# Sheet1.net
KiCad netlist of a schematic drawn in Altium Designer
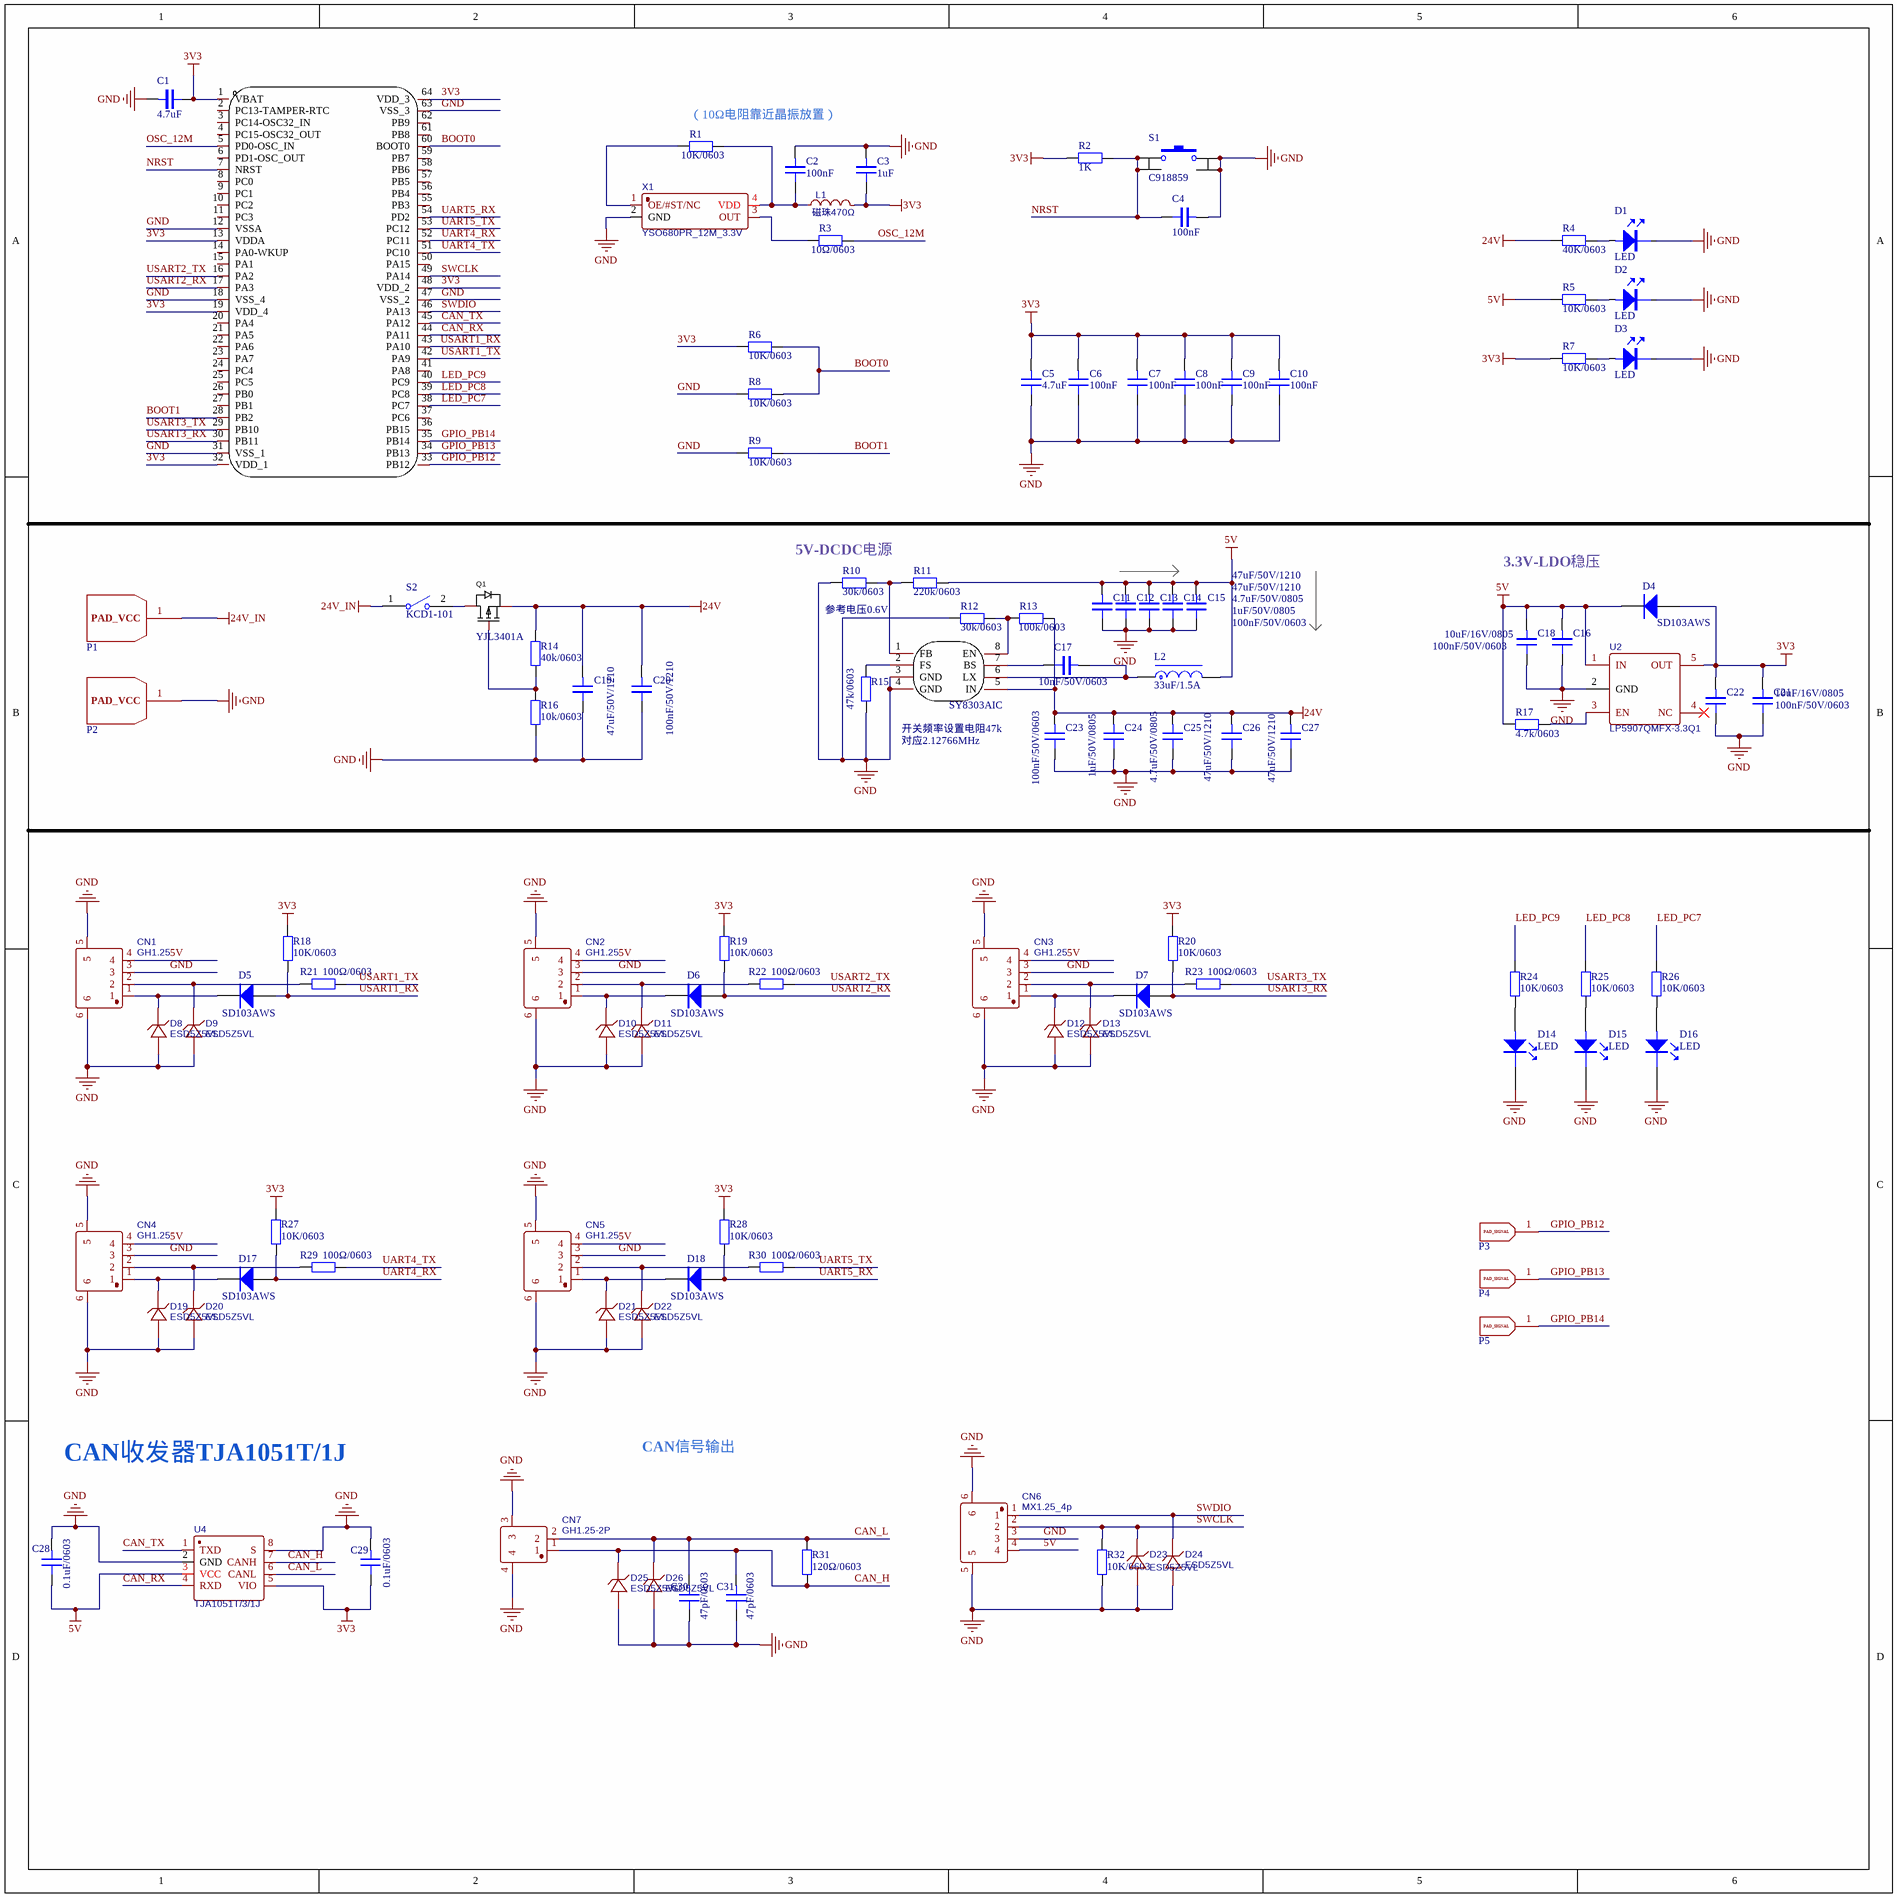
[diagram p0: Sheet1.SchDoc]

(export (version "E")
  (design (tool "Eeschema 10.0.6"))
  (components
    (comp (ref "C1")
      (value "4.7uF")
      (footprint "C 0603_L")
      (description "陶瓷电容")
      (libsource (lib "HERO_通用") (part "CAP"))
    )
    (comp (ref "C2")
      (value "100nF")
      (footprint "C 0603_L")
      (description "陶瓷电容")
      (libsource (lib "HERO_通用") (part "CAP"))
    )
    (comp (ref "C3")
      (value "1uF")
      (footprint "C 0603_L")
      (description "陶瓷电容")
      (libsource (lib "HERO_通用") (part "CAP"))
    )
    (comp (ref "C4")
      (value "100nF")
      (footprint "C 0603_L")
      (description "陶瓷电容")
      (libsource (lib "HERO_通用") (part "CAP"))
    )
    (comp (ref "C5")
      (value "4.7uF")
      (footprint "C 0603_L")
      (description "陶瓷电容")
      (libsource (lib "HERO_通用") (part "CAP"))
    )
    (comp (ref "C6")
      (value "100nF")
      (footprint "C 0603_L")
      (description "陶瓷电容")
      (libsource (lib "HERO_通用") (part "CAP"))
    )
    (comp (ref "C7")
      (value "100nF")
      (footprint "C 0603_L")
      (description "陶瓷电容")
      (libsource (lib "HERO_通用") (part "CAP"))
    )
    (comp (ref "C8")
      (value "100nF")
      (footprint "C 0603_L")
      (description "陶瓷电容")
      (libsource (lib "HERO_通用") (part "CAP"))
    )
    (comp (ref "C9")
      (value "100nF")
      (footprint "C 0603_L")
      (description "陶瓷电容")
      (libsource (lib "HERO_通用") (part "CAP"))
    )
    (comp (ref "C10")
      (value "100nF")
      (footprint "C 0603_L")
      (description "陶瓷电容")
      (libsource (lib "HERO_通用") (part "CAP"))
    )
    (comp (ref "C11")
      (value "47uF/50V/1210")
      (footprint "C 1210_L")
      (description "陶瓷电容")
      (libsource (lib "HERO_通用") (part "CAP"))
    )
    (comp (ref "C12")
      (value "47uF/50V/1210")
      (footprint "C 1210_L")
      (description "陶瓷电容")
      (libsource (lib "HERO_通用") (part "CAP"))
    )
    (comp (ref "C13")
      (value "4.7uF/50V/0805")
      (footprint "C 0805_L")
      (description "陶瓷电容")
      (libsource (lib "HERO_通用") (part "CAP"))
    )
    (comp (ref "C14")
      (value "1uF/50V/0805")
      (footprint "C 0805_L")
      (description "陶瓷电容")
      (libsource (lib "HERO_通用") (part "CAP"))
    )
    (comp (ref "C15")
      (value "100nF/50V/0603")
      (footprint "C 0603_L")
      (description "陶瓷电容")
      (libsource (lib "HERO_通用") (part "CAP"))
    )
    (comp (ref "C16")
      (value "100nF/50V/0603")
      (footprint "C 0603_L")
      (description "Capacitor")
      (libsource (lib "DJI_Armer") (part "CAP"))
    )
    (comp (ref "C17")
      (value "10nF/50V/0603")
      (footprint "C 0603_L")
      (description "陶瓷电容")
      (libsource (lib "HERO_通用") (part "CAP"))
    )
    (comp (ref "C18")
      (value "10uF/16V/0805")
      (footprint "C 0805_L")
      (description "陶瓷电容")
      (libsource (lib "HERO_通用") (part "CAP"))
    )
    (comp (ref "C19")
      (value "47uF/50V/1210")
      (footprint "C 1210_L")
      (description "陶瓷电容")
      (libsource (lib "HERO_通用") (part "CAP"))
    )
    (comp (ref "C20")
      (value "100nF/50V/1210")
      (footprint "C 0603_L")
      (description "陶瓷电容")
      (libsource (lib "HERO_通用") (part "CAP"))
    )
    (comp (ref "C21")
      (value "100nF/50V/0603")
      (footprint "C 0603_L")
      (description "Capacitor")
      (libsource (lib "DJI_Armer") (part "CAP"))
    )
    (comp (ref "C22")
      (value "10uF/16V/0805")
      (footprint "C 0805_L")
      (description "陶瓷电容")
      (libsource (lib "HERO_通用") (part "CAP"))
    )
    (comp (ref "C23")
      (value "100nF/50V/0603")
      (footprint "C 0603_L")
      (description "陶瓷电容")
      (libsource (lib "HERO_通用") (part "CAP"))
    )
    (comp (ref "C24")
      (value "1uF/50V/0805")
      (footprint "C 0805_L")
      (description "陶瓷电容")
      (libsource (lib "HERO_通用") (part "CAP"))
    )
    (comp (ref "C25")
      (value "4.7uF/50V/0805")
      (footprint "C 0805_L")
      (description "陶瓷电容")
      (libsource (lib "HERO_通用") (part "CAP"))
    )
    (comp (ref "C26")
      (value "47uF/50V/1210")
      (footprint "C 1210_L")
      (description "陶瓷电容")
      (libsource (lib "HERO_通用") (part "CAP"))
    )
    (comp (ref "C27")
      (value "47uF/50V/1210")
      (footprint "C 1210_L")
      (description "陶瓷电容")
      (libsource (lib "HERO_通用") (part "CAP"))
    )
    (comp (ref "C28")
      (value "0.1uF/0603")
      (footprint "C 0603_L")
      (description "陶瓷电容")
      (libsource (lib "HERO_通用") (part "CAP"))
    )
    (comp (ref "C29")
      (value "0.1uF/0603")
      (footprint "C 0603_L")
      (description "陶瓷电容")
      (libsource (lib "HERO_通用") (part "CAP"))
    )
    (comp (ref "C30")
      (value "47pF/0603")
      (footprint "C 0603_L")
      (description "陶瓷电容")
      (libsource (lib "HERO_通用") (part "CAP"))
    )
    (comp (ref "C31")
      (value "47pF/0603")
      (footprint "C 0603_L")
      (description "陶瓷电容")
      (libsource (lib "HERO_通用") (part "CAP"))
    )
    (comp (ref "CN1")
      (value "GH1.25")
      (footprint "GH1.25 4P-WT")
      (description "连接端子")
      (fields
        (field (name "BOM_SUPPLIER PART") "C225127")
        (field (name "BOM_MANUFACTURER PART") "A1257WR-S-4P")
        (field (name "CONTRIBUTOR") "LCSC")
      )
      (libsource (lib "HERO_交互") (part "GH1.25 4p"))
    )
    (comp (ref "CN2")
      (value "GH1.25")
      (footprint "GH1.25 4P-WT")
      (description "连接端子")
      (fields
        (field (name "BOM_SUPPLIER PART") "C225127")
        (field (name "BOM_MANUFACTURER PART") "A1257WR-S-4P")
        (field (name "CONTRIBUTOR") "LCSC")
      )
      (libsource (lib "HERO_交互") (part "GH1.25 4p"))
    )
    (comp (ref "CN3")
      (value "GH1.25")
      (footprint "GH1.25 4P-WT")
      (description "连接端子")
      (fields
        (field (name "BOM_SUPPLIER PART") "C225127")
        (field (name "BOM_MANUFACTURER PART") "A1257WR-S-4P")
        (field (name "CONTRIBUTOR") "LCSC")
      )
      (libsource (lib "HERO_交互") (part "GH1.25 4p"))
    )
    (comp (ref "CN4")
      (value "GH1.25")
      (footprint "GH1.25 4P-WT")
      (description "连接端子")
      (fields
        (field (name "BOM_SUPPLIER PART") "C225127")
        (field (name "BOM_MANUFACTURER PART") "A1257WR-S-4P")
        (field (name "CONTRIBUTOR") "LCSC")
      )
      (libsource (lib "HERO_交互") (part "GH1.25 4p"))
    )
    (comp (ref "CN5")
      (value "GH1.25")
      (footprint "GH1.25 4P-WT")
      (description "连接端子")
      (fields
        (field (name "BOM_SUPPLIER PART") "C225127")
        (field (name "BOM_MANUFACTURER PART") "A1257WR-S-4P")
        (field (name "CONTRIBUTOR") "LCSC")
      )
      (libsource (lib "HERO_交互") (part "GH1.25 4p"))
    )
    (comp (ref "CN6")
      (value "MX1.25_4p")
      (footprint "MX1.25_4PIN")
      (description "连接端子")
      (fields
        (field (name "BOM_SUPPLIER PART") "C225127")
        (field (name "BOM_MANUFACTURER PART") "A1257WR-S-4P")
        (field (name "CONTRIBUTOR") "LCSC")
      )
      (libsource (lib "HERO_交互") (part "MX1.25_4p"))
    )
    (comp (ref "CN7")
      (value "GH1.25-2P")
      (footprint "GH1.25-2P-LT")
      (description "连接端子")
      (fields
        (field (name "BOM_SUPPLIER PART") "C225125")
        (field (name "BOM_MANUFACTURER PART") "A1257WR-S-2P")
        (field (name "CONTRIBUTOR") "LCSC")
      )
      (libsource (lib "HERO_交互") (part "GH1.25-2P"))
    )
    (comp (ref "D1")
      (value "LED")
      (footprint "LED_0603")
      (description "发光二极管")
      (libsource (lib "") (part "LED_1"))
    )
    (comp (ref "D2")
      (value "LED")
      (footprint "LED_0603")
      (description "发光二极管")
      (libsource (lib "") (part "LED_1"))
    )
    (comp (ref "D3")
      (value "LED")
      (footprint "LED_0603")
      (description "发光二极管")
      (libsource (lib "") (part "LED_1"))
    )
    (comp (ref "D4")
      (value "SD103AWS")
      (footprint "SOD-323")
      (description "二极管")
      (libsource (lib "DJI_Armer") (part "SD103AWS"))
    )
    (comp (ref "D5")
      (value "SD103AWS")
      (footprint "SOD-323")
      (description "二极管")
      (libsource (lib "DJI_Armer") (part "SD103AWS"))
    )
    (comp (ref "D6")
      (value "SD103AWS")
      (footprint "SOD-323")
      (description "二极管")
      (libsource (lib "DJI_Armer") (part "SD103AWS"))
    )
    (comp (ref "D7")
      (value "SD103AWS")
      (footprint "SOD-323")
      (description "二极管")
      (libsource (lib "DJI_Armer") (part "SD103AWS"))
    )
    (comp (ref "D8")
      (value "ESD5Z5VL")
      (footprint "SOD-523")
      (description "ESD 单向 5V")
      (fields
        (field (name "BOM_MANUFACTURER PART") "SMF6.5A")
        (field (name "BOM_SUPPLIER PART") "C123792")
        (field (name "CONTRIBUTOR") "LCSC")
      )
      (libsource (lib "HERO_通用") (part "ESD5Z5VL"))
    )
    (comp (ref "D9")
      (value "ESD5Z5VL")
      (footprint "SOD-523")
      (description "ESD 单向 5V")
      (fields
        (field (name "BOM_MANUFACTURER PART") "SMF6.5A")
        (field (name "BOM_SUPPLIER PART") "C123792")
        (field (name "CONTRIBUTOR") "LCSC")
      )
      (libsource (lib "HERO_通用") (part "ESD5Z5VL"))
    )
    (comp (ref "D10")
      (value "ESD5Z5VL")
      (footprint "SOD-523")
      (description "ESD 单向 5V")
      (fields
        (field (name "BOM_MANUFACTURER PART") "SMF6.5A")
        (field (name "BOM_SUPPLIER PART") "C123792")
        (field (name "CONTRIBUTOR") "LCSC")
      )
      (libsource (lib "HERO_通用") (part "ESD5Z5VL"))
    )
    (comp (ref "D11")
      (value "ESD5Z5VL")
      (footprint "SOD-523")
      (description "ESD 单向 5V")
      (fields
        (field (name "BOM_MANUFACTURER PART") "SMF6.5A")
        (field (name "BOM_SUPPLIER PART") "C123792")
        (field (name "CONTRIBUTOR") "LCSC")
      )
      (libsource (lib "HERO_通用") (part "ESD5Z5VL"))
    )
    (comp (ref "D12")
      (value "ESD5Z5VL")
      (footprint "SOD-523")
      (description "ESD 单向 5V")
      (fields
        (field (name "BOM_MANUFACTURER PART") "SMF6.5A")
        (field (name "BOM_SUPPLIER PART") "C123792")
        (field (name "CONTRIBUTOR") "LCSC")
      )
      (libsource (lib "HERO_通用") (part "ESD5Z5VL"))
    )
    (comp (ref "D13")
      (value "ESD5Z5VL")
      (footprint "SOD-523")
      (description "ESD 单向 5V")
      (fields
        (field (name "BOM_MANUFACTURER PART") "SMF6.5A")
        (field (name "BOM_SUPPLIER PART") "C123792")
        (field (name "CONTRIBUTOR") "LCSC")
      )
      (libsource (lib "HERO_通用") (part "ESD5Z5VL"))
    )
    (comp (ref "D14")
      (value "LED")
      (footprint "LED_0603")
      (description "发光二极管")
      (libsource (lib "HERO_通用") (part "LED"))
    )
    (comp (ref "D15")
      (value "LED")
      (footprint "LED_0603")
      (description "发光二极管")
      (libsource (lib "HERO_通用") (part "LED"))
    )
    (comp (ref "D16")
      (value "LED")
      (footprint "LED_0603")
      (description "发光二极管")
      (libsource (lib "HERO_通用") (part "LED"))
    )
    (comp (ref "D17")
      (value "SD103AWS")
      (footprint "SOD-323")
      (description "二极管")
      (libsource (lib "DJI_Armer") (part "SD103AWS"))
    )
    (comp (ref "D18")
      (value "SD103AWS")
      (footprint "SOD-323")
      (description "二极管")
      (libsource (lib "DJI_Armer") (part "SD103AWS"))
    )
    (comp (ref "D19")
      (value "ESD5Z5VL")
      (footprint "SOD-523")
      (description "ESD 单向 5V")
      (fields
        (field (name "BOM_MANUFACTURER PART") "SMF6.5A")
        (field (name "BOM_SUPPLIER PART") "C123792")
        (field (name "CONTRIBUTOR") "LCSC")
      )
      (libsource (lib "HERO_通用") (part "ESD5Z5VL"))
    )
    (comp (ref "D20")
      (value "ESD5Z5VL")
      (footprint "SOD-523")
      (description "ESD 单向 5V")
      (fields
        (field (name "BOM_MANUFACTURER PART") "SMF6.5A")
        (field (name "BOM_SUPPLIER PART") "C123792")
        (field (name "CONTRIBUTOR") "LCSC")
      )
      (libsource (lib "HERO_通用") (part "ESD5Z5VL"))
    )
    (comp (ref "D21")
      (value "ESD5Z5VL")
      (footprint "SOD-523")
      (description "ESD 单向 5V")
      (fields
        (field (name "BOM_MANUFACTURER PART") "SMF6.5A")
        (field (name "BOM_SUPPLIER PART") "C123792")
        (field (name "CONTRIBUTOR") "LCSC")
      )
      (libsource (lib "HERO_通用") (part "ESD5Z5VL"))
    )
    (comp (ref "D22")
      (value "ESD5Z5VL")
      (footprint "SOD-523")
      (description "ESD 单向 5V")
      (fields
        (field (name "BOM_MANUFACTURER PART") "SMF6.5A")
        (field (name "BOM_SUPPLIER PART") "C123792")
        (field (name "CONTRIBUTOR") "LCSC")
      )
      (libsource (lib "HERO_通用") (part "ESD5Z5VL"))
    )
    (comp (ref "D23")
      (value "ESD5Z5VL")
      (footprint "SOD-523")
      (description "ESD 单向 5V")
      (fields
        (field (name "BOM_MANUFACTURER PART") "SMF6.5A")
        (field (name "BOM_SUPPLIER PART") "C123792")
        (field (name "CONTRIBUTOR") "LCSC")
      )
      (libsource (lib "HERO_通用") (part "ESD5Z5VL"))
    )
    (comp (ref "D24")
      (value "ESD5Z5VL")
      (footprint "SOD-523")
      (description "ESD 单向 5V")
      (fields
        (field (name "BOM_MANUFACTURER PART") "SMF6.5A")
        (field (name "BOM_SUPPLIER PART") "C123792")
        (field (name "CONTRIBUTOR") "LCSC")
      )
      (libsource (lib "HERO_通用") (part "ESD5Z5VL"))
    )
    (comp (ref "D25")
      (value "ESD5Z5VL")
      (footprint "SOD-523")
      (description "ESD 单向 5V")
      (fields
        (field (name "BOM_MANUFACTURER PART") "SMF6.5A")
        (field (name "BOM_SUPPLIER PART") "C123792")
        (field (name "CONTRIBUTOR") "LCSC")
      )
      (libsource (lib "HERO_通用") (part "ESD5Z5VL"))
    )
    (comp (ref "D26")
      (value "ESD5Z5VL")
      (footprint "SOD-523")
      (description "ESD 单向 5V")
      (fields
        (field (name "BOM_MANUFACTURER PART") "SMF6.5A")
        (field (name "BOM_SUPPLIER PART") "C123792")
        (field (name "CONTRIBUTOR") "LCSC")
      )
      (libsource (lib "HERO_通用") (part "ESD5Z5VL"))
    )
    (comp (ref "L1")
      (value "磁珠470Ω")
      (footprint "C 0603_L")
      (fields
        (field (name "BOM_MANUFACTURER PART") "UPZ1608U471-1R5TF")
        (field (name "BOM_SUPPLIER PART") "C74335")
      )
      (libsource (lib "HERO_通用") (part "磁珠470Ω"))
    )
    (comp (ref "L2")
      (value "33uF/1.5A")
      (footprint "IND-SMD_L7.3-W7.3")
      (description "贴片功率电感")
      (libsource (lib "Schlib1") (part "L-SMD"))
    )
    (comp (ref "P1") (value "PAD_VCC") (footprint "PAD_VCC") (libsource (lib "HERO_模块") (part "PAD_VCC")))
    (comp (ref "P2") (value "PAD_VCC") (footprint "PAD_VCC") (libsource (lib "HERO_模块") (part "PAD_VCC")))
    (comp (ref "P3")
      (value "PAD_Signal")
      (footprint "pad_signal")
      (libsource (lib "HERO_模块") (part "PAD_Signal"))
    )
    (comp (ref "P4")
      (value "PAD_Signal")
      (footprint "pad_signal")
      (libsource (lib "HERO_模块") (part "PAD_Signal"))
    )
    (comp (ref "P5")
      (value "PAD_Signal")
      (footprint "pad_signal")
      (libsource (lib "HERO_模块") (part "PAD_Signal"))
    )
    (comp (ref "Q1")
      (value "YJL3401A")
      (footprint "SOT-23-3_L2.9-W1.3-P1.90-LS2.4-BR")
      (fields (field (name "MANUFACTURER") "YANGJIE(扬杰)"))
      (libsource (lib "EG_slave_STCG12") (part "YJL3401A"))
    )
    (comp (ref "R1")
      (value "10K/0603")
      (footprint "R 0603_S")
      (description "贴片电阻")
      (libsource (lib "HERO_通用") (part "RES"))
    )
    (comp (ref "R2")
      (value "1K")
      (footprint "R 0603_S")
      (description "贴片电阻")
      (libsource (lib "HERO_通用") (part "RES"))
    )
    (comp (ref "R3")
      (value "10Ω/0603")
      (footprint "R 0603_S")
      (description "贴片电阻")
      (libsource (lib "HERO_通用") (part "RES"))
    )
    (comp (ref "R4")
      (value "40K/0603")
      (footprint "R 0603_S")
      (description "贴片电阻")
      (libsource (lib "HERO_通用") (part "RES"))
    )
    (comp (ref "R5")
      (value "10K/0603")
      (footprint "R 0603_S")
      (description "贴片电阻")
      (libsource (lib "HERO_通用") (part "RES"))
    )
    (comp (ref "R6")
      (value "10K/0603")
      (footprint "R 0603_S")
      (description "贴片电阻")
      (libsource (lib "HERO_通用") (part "RES"))
    )
    (comp (ref "R7")
      (value "10K/0603")
      (footprint "R 0603_S")
      (description "贴片电阻")
      (libsource (lib "HERO_通用") (part "RES"))
    )
    (comp (ref "R8")
      (value "10K/0603")
      (footprint "R 0603_S")
      (description "贴片电阻")
      (libsource (lib "HERO_通用") (part "RES"))
    )
    (comp (ref "R9")
      (value "10K/0603")
      (footprint "R 0603_S")
      (description "贴片电阻")
      (libsource (lib "HERO_通用") (part "RES"))
    )
    (comp (ref "R10")
      (value "30k/0603")
      (footprint "R 0603_S")
      (description "贴片电阻")
      (libsource (lib "HERO_通用") (part "RES"))
    )
    (comp (ref "R11")
      (value "220k/0603")
      (footprint "R 0603_S")
      (description "贴片电阻")
      (libsource (lib "HERO_通用") (part "RES"))
    )
    (comp (ref "R12")
      (value "30k/0603")
      (footprint "R 0603_S")
      (description "贴片电阻")
      (libsource (lib "HERO_通用") (part "RES"))
    )
    (comp (ref "R13")
      (value "100k/0603")
      (footprint "R 0603_S")
      (description "贴片电阻")
      (libsource (lib "HERO_通用") (part "RES"))
    )
    (comp (ref "R14")
      (value "40k/0603")
      (footprint "R 0603_S")
      (description "贴片电阻")
      (libsource (lib "") (part "RES_1"))
    )
    (comp (ref "R15")
      (value "47k/0603")
      (footprint "R 0603_S")
      (description "贴片电阻")
      (libsource (lib "") (part "RES_1"))
    )
    (comp (ref "R16")
      (value "10k/0603")
      (footprint "R 0603_S")
      (description "贴片电阻")
      (libsource (lib "") (part "RES_1"))
    )
    (comp (ref "R17")
      (value "4.7k/0603")
      (footprint "R 0603_S")
      (description "贴片电阻")
      (libsource (lib "HERO_通用") (part "RES"))
    )
    (comp (ref "R18")
      (value "10K/0603")
      (footprint "R 0603_S")
      (description "贴片电阻")
      (libsource (lib "") (part "RES_1"))
    )
    (comp (ref "R19")
      (value "10K/0603")
      (footprint "R 0603_S")
      (description "贴片电阻")
      (libsource (lib "") (part "RES_1"))
    )
    (comp (ref "R20")
      (value "10K/0603")
      (footprint "R 0603_S")
      (description "贴片电阻")
      (libsource (lib "") (part "RES_1"))
    )
    (comp (ref "R21")
      (value "100Ω/0603")
      (footprint "R 0603_S")
      (description "贴片电阻")
      (libsource (lib "HERO_通用") (part "RES"))
    )
    (comp (ref "R22")
      (value "100Ω/0603")
      (footprint "R 0603_S")
      (description "贴片电阻")
      (libsource (lib "HERO_通用") (part "RES"))
    )
    (comp (ref "R23")
      (value "100Ω/0603")
      (footprint "R 0603_S")
      (description "贴片电阻")
      (libsource (lib "HERO_通用") (part "RES"))
    )
    (comp (ref "R24")
      (value "10K/0603")
      (footprint "R 0603_S")
      (description "贴片电阻")
      (libsource (lib "") (part "RES_1"))
    )
    (comp (ref "R25")
      (value "10K/0603")
      (footprint "R 0603_S")
      (description "贴片电阻")
      (libsource (lib "") (part "RES_1"))
    )
    (comp (ref "R26")
      (value "10K/0603")
      (footprint "R 0603_S")
      (description "贴片电阻")
      (libsource (lib "") (part "RES_1"))
    )
    (comp (ref "R27")
      (value "10K/0603")
      (footprint "R 0603_S")
      (description "贴片电阻")
      (libsource (lib "") (part "RES_1"))
    )
    (comp (ref "R28")
      (value "10K/0603")
      (footprint "R 0603_S")
      (description "贴片电阻")
      (libsource (lib "") (part "RES_1"))
    )
    (comp (ref "R29")
      (value "100Ω/0603")
      (footprint "R 0603_S")
      (description "贴片电阻")
      (libsource (lib "HERO_通用") (part "RES"))
    )
    (comp (ref "R30")
      (value "100Ω/0603")
      (footprint "R 0603_S")
      (description "贴片电阻")
      (libsource (lib "HERO_通用") (part "RES"))
    )
    (comp (ref "R31")
      (value "120Ω/0603")
      (footprint "R 0603_S")
      (description "贴片电阻")
      (libsource (lib "") (part "RES_1"))
    )
    (comp (ref "R32")
      (value "10K/0603")
      (footprint "R 0603_S")
      (description "贴片电阻")
      (libsource (lib "") (part "RES_1"))
    )
    (comp (ref "S1")
      (value "C918859")
      (footprint "KEY-4.2*3.25")
      (description "DJI御用小按键")
      (libsource (lib "HERO_交互") (part "按键"))
    )
    (comp (ref "S2")
      (value "KCD1-101")
      (footprint "SW-TH_MR5-111-C5N-BB")
      (description "单刀单掷 直插立式")
      (libsource (lib "HERO_交互") (part "KCD1-101"))
    )
    (comp (ref "U1")
      (value "STM32F103RCT6")
      (footprint "LQFP-64_L10.0-W10.0-P0.50-LS12.0-BL")
      (fields (field (name "MANUFACTURER") "ST(意法半导体)"))
      (libsource (lib "Schlib1") (part "STM32F103RCT6"))
    )
    (comp (ref "U2")
      (value "LP5907QMFX-3.3Q1")
      (footprint "SOT23-5N")
      (fields (field (name "BOM_SUPPLIER PART") "C130005") (field (name "CONTRIBUTOR") "LCSC"))
      (libsource (lib "DJI_Armer") (part "LP5907QMFX-3.3Q1"))
    )
    (comp (ref "U3")
      (value "SY8303AIC")
      (footprint "TSOT-23-8_L2.9-W1.6-P0.65-LS2.8-BR")
      (description "DCDC ADJ 3A")
      (fields (field (name "MANUFACTURER") "矽力杰silergy"))
      (libsource (lib "HERO_IC") (part "SY8303AIC"))
    )
    (comp (ref "U4")
      (value "TJA1051T/3/1J")
      (footprint "SOP8_L")
      (description "CAN芯片")
      (fields (field (name "BOM_SUPPLIER PART") "C38695"))
      (libsource (lib "HERO_IC") (part "TJA1051T/3/1J"))
    )
    (comp (ref "X1")
      (value "YSO680PR_12M_3.3V")
      (footprint "OSC 3225-4P")
      (description "有源晶振12M")
      (fields
        (field (name "BOM_SUPPLIER PART") "C382483")
        (field (name "BOM_MANUFACTURER PART") "OP322512MEDA4SI-u")
        (field (name "CONTRIBUTOR") "LCSC")
      )
      (libsource (lib "HERO_IC") (part "YSO680PR_12M_3.3V"))
    )
  )
  (nets
    (net (code "1") (name "/BOOT0") (class "Default")
      (node (ref "R6") (pin "2") (pinfunction "2_2") (pintype "passive"))
      (node (ref "R8") (pin "2") (pinfunction "2_2") (pintype "passive"))
      (node (ref "U1") (pin "60") (pinfunction "BOOT0_60") (pintype "passive"))
    )
    (net (code "2") (name "/BOOT1") (class "Default")
      (node (ref "R9") (pin "2") (pinfunction "2_2") (pintype "passive"))
      (node (ref "U1") (pin "28") (pinfunction "PB2_28") (pintype "passive"))
    )
    (net (code "3") (name "/CAN_H") (class "Default")
      (node (ref "C31") (pin "1") (pinfunction "1_1") (pintype "passive"))
      (node (ref "CN7") (pin "1") (pinfunction "1_1") (pintype "passive"))
      (node (ref "D25") (pin "2") (pinfunction "C_2") (pintype "passive"))
      (node (ref "R31") (pin "2") (pinfunction "2_2") (pintype "passive"))
      (node (ref "U4") (pin "7") (pinfunction "CANH_7") (pintype "passive"))
    )
    (net (code "4") (name "/CAN_L") (class "Default")
      (node (ref "C30") (pin "1") (pinfunction "1_1") (pintype "passive"))
      (node (ref "CN7") (pin "2") (pinfunction "2_2") (pintype "passive"))
      (node (ref "D26") (pin "2") (pinfunction "C_2") (pintype "passive"))
      (node (ref "R31") (pin "1") (pinfunction "1_1") (pintype "passive"))
      (node (ref "U4") (pin "6") (pinfunction "CANL_6") (pintype "passive"))
    )
    (net (code "5") (name "/CAN_RX") (class "Default")
      (node (ref "U1") (pin "44") (pinfunction "PA11_44") (pintype "passive"))
      (node (ref "U4") (pin "4") (pinfunction "RXD_4") (pintype "passive"))
    )
    (net (code "6") (name "/CAN_TX") (class "Default")
      (node (ref "U1") (pin "45") (pinfunction "PA12_45") (pintype "passive"))
      (node (ref "U4") (pin "1") (pinfunction "TXD_1") (pintype "passive"))
    )
    (net (code "7") (name "/GPIO_PB12") (class "Default")
      (node (ref "P3") (pin "1") (pinfunction "PAD_SIGNAL_1") (pintype "passive"))
      (node (ref "U1") (pin "33") (pinfunction "PB12_33") (pintype "passive"))
    )
    (net (code "8") (name "/GPIO_PB13") (class "Default")
      (node (ref "P4") (pin "1") (pinfunction "PAD_SIGNAL_1") (pintype "passive"))
      (node (ref "U1") (pin "34") (pinfunction "PB13_34") (pintype "passive"))
    )
    (net (code "9") (name "/GPIO_PB14") (class "Default")
      (node (ref "P5") (pin "1") (pinfunction "PAD_SIGNAL_1") (pintype "passive"))
      (node (ref "U1") (pin "35") (pinfunction "PB14_35") (pintype "passive"))
    )
    (net (code "10") (name "/LED_PC7") (class "Default")
      (node (ref "R26") (pin "1") (pinfunction "1_1") (pintype "passive"))
      (node (ref "U1") (pin "38") (pinfunction "PC7_38") (pintype "passive"))
    )
    (net (code "11") (name "/LED_PC8") (class "Default")
      (node (ref "R25") (pin "1") (pinfunction "1_1") (pintype "passive"))
      (node (ref "U1") (pin "39") (pinfunction "PC8_39") (pintype "passive"))
    )
    (net (code "12") (name "/LED_PC9") (class "Default")
      (node (ref "R24") (pin "1") (pinfunction "1_1") (pintype "passive"))
      (node (ref "U1") (pin "40") (pinfunction "PC9_40") (pintype "passive"))
    )
    (net (code "13") (name "/NRST") (class "Default")
      (node (ref "C4") (pin "2") (pinfunction "2_2") (pintype "passive"))
      (node (ref "R2") (pin "2") (pinfunction "2_2") (pintype "passive"))
      (node (ref "S1") (pin "1") (pinfunction "1_1") (pintype "passive"))
      (node (ref "S1") (pin "2") (pinfunction "2_2") (pintype "passive"))
      (node (ref "U1") (pin "7") (pinfunction "NRST_7") (pintype "passive"))
    )
    (net (code "14") (name "/OSC_12M") (class "Default")
      (node (ref "R3") (pin "2") (pinfunction "2_2") (pintype "passive"))
      (node (ref "U1") (pin "5") (pinfunction "PD0-OSC_IN_5") (pintype "passive"))
    )
    (net (code "15") (name "/SWCLK") (class "Default")
      (node (ref "CN6") (pin "2") (pinfunction "2_2") (pintype "passive"))
      (node (ref "D23") (pin "2") (pinfunction "C_2") (pintype "passive"))
      (node (ref "R32") (pin "1") (pinfunction "1_1") (pintype "passive"))
      (node (ref "U1") (pin "49") (pinfunction "PA14_49") (pintype "passive"))
    )
    (net (code "16") (name "/SWDIO") (class "Default")
      (node (ref "CN6") (pin "1") (pinfunction "1_1") (pintype "passive"))
      (node (ref "D24") (pin "2") (pinfunction "C_2") (pintype "passive"))
      (node (ref "U1") (pin "46") (pinfunction "PA13_46") (pintype "passive"))
    )
    (net (code "17") (name "/UART4_RX") (class "Default")
      (node (ref "D17") (pin "1") (pinfunction "1_1") (pintype "passive"))
      (node (ref "R27") (pin "2") (pinfunction "2_2") (pintype "passive"))
      (node (ref "U1") (pin "52") (pinfunction "PC11_52") (pintype "passive"))
    )
    (net (code "18") (name "/UART4_TX") (class "Default")
      (node (ref "R29") (pin "2") (pinfunction "2_2") (pintype "passive"))
      (node (ref "U1") (pin "51") (pinfunction "PC10_51") (pintype "passive"))
    )
    (net (code "19") (name "/UART5_RX") (class "Default")
      (node (ref "D18") (pin "1") (pinfunction "1_1") (pintype "passive"))
      (node (ref "R28") (pin "2") (pinfunction "2_2") (pintype "passive"))
      (node (ref "U1") (pin "54") (pinfunction "PD2_54") (pintype "passive"))
    )
    (net (code "20") (name "/UART5_TX") (class "Default")
      (node (ref "R30") (pin "2") (pinfunction "2_2") (pintype "passive"))
      (node (ref "U1") (pin "53") (pinfunction "PC12_53") (pintype "passive"))
    )
    (net (code "21") (name "/USART1_RX") (class "Default")
      (node (ref "D5") (pin "1") (pinfunction "1_1") (pintype "passive"))
      (node (ref "R18") (pin "2") (pinfunction "2_2") (pintype "passive"))
      (node (ref "U1") (pin "43") (pinfunction "PA10_43") (pintype "passive"))
    )
    (net (code "22") (name "/USART1_TX") (class "Default")
      (node (ref "R21") (pin "2") (pinfunction "2_2") (pintype "passive"))
      (node (ref "U1") (pin "42") (pinfunction "PA9_42") (pintype "passive"))
    )
    (net (code "23") (name "/USART2_RX") (class "Default")
      (node (ref "D6") (pin "1") (pinfunction "1_1") (pintype "passive"))
      (node (ref "R19") (pin "2") (pinfunction "2_2") (pintype "passive"))
      (node (ref "U1") (pin "17") (pinfunction "PA3_17") (pintype "passive"))
    )
    (net (code "24") (name "/USART2_TX") (class "Default")
      (node (ref "R22") (pin "2") (pinfunction "2_2") (pintype "passive"))
      (node (ref "U1") (pin "16") (pinfunction "PA2_16") (pintype "passive"))
    )
    (net (code "25") (name "/USART3_RX") (class "Default")
      (node (ref "D7") (pin "1") (pinfunction "1_1") (pintype "passive"))
      (node (ref "R20") (pin "2") (pinfunction "2_2") (pintype "passive"))
      (node (ref "U1") (pin "30") (pinfunction "PB11_30") (pintype "passive"))
    )
    (net (code "26") (name "/USART3_TX") (class "Default")
      (node (ref "R23") (pin "2") (pinfunction "2_2") (pintype "passive"))
      (node (ref "U1") (pin "29") (pinfunction "PB10_29") (pintype "passive"))
    )
    (net (code "27") (name "3V3") (class "Default")
      (node (ref "C1") (pin "2") (pinfunction "2_2") (pintype "passive"))
      (node (ref "C10") (pin "1") (pinfunction "1_1") (pintype "passive"))
      (node (ref "C21") (pin "1") (pinfunction "1_1") (pintype "passive"))
      (node (ref "C22") (pin "1") (pinfunction "1_1") (pintype "passive"))
      (node (ref "C29") (pin "2") (pinfunction "2_2") (pintype "passive"))
      (node (ref "C3") (pin "2") (pinfunction "2_2") (pintype "passive"))
      (node (ref "C5") (pin "1") (pinfunction "1_1") (pintype "passive"))
      (node (ref "C6") (pin "1") (pinfunction "1_1") (pintype "passive"))
      (node (ref "C7") (pin "1") (pinfunction "1_1") (pintype "passive"))
      (node (ref "C8") (pin "1") (pinfunction "1_1") (pintype "passive"))
      (node (ref "C9") (pin "1") (pinfunction "1_1") (pintype "passive"))
      (node (ref "D4") (pin "1") (pinfunction "1_1") (pintype "passive"))
      (node (ref "L1") (pin "2") (pinfunction "2_2") (pintype "passive"))
      (node (ref "R18") (pin "1") (pinfunction "1_1") (pintype "passive"))
      (node (ref "R19") (pin "1") (pinfunction "1_1") (pintype "passive"))
      (node (ref "R2") (pin "1") (pinfunction "1_1") (pintype "passive"))
      (node (ref "R20") (pin "1") (pinfunction "1_1") (pintype "passive"))
      (node (ref "R27") (pin "1") (pinfunction "1_1") (pintype "passive"))
      (node (ref "R28") (pin "1") (pinfunction "1_1") (pintype "passive"))
      (node (ref "R6") (pin "1") (pinfunction "1_1") (pintype "passive"))
      (node (ref "R7") (pin "1") (pinfunction "1_1") (pintype "passive"))
      (node (ref "U1") (pin "1") (pinfunction "VBAT_1") (pintype "passive"))
      (node (ref "U1") (pin "13") (pinfunction "VDDA_13") (pintype "passive"))
      (node (ref "U1") (pin "19") (pinfunction "VDD_4_19") (pintype "passive"))
      (node (ref "U1") (pin "32") (pinfunction "VDD_1_32") (pintype "passive"))
      (node (ref "U1") (pin "48") (pinfunction "VDD_2_48") (pintype "passive"))
      (node (ref "U1") (pin "64") (pinfunction "VDD_3_64") (pintype "passive"))
      (node (ref "U2") (pin "5") (pinfunction "OUT_5") (pintype "passive"))
      (node (ref "U4") (pin "5") (pinfunction "VIO_5") (pintype "passive"))
    )
    (net (code "28") (name "5V") (class "Default")
      (node (ref "C11") (pin "1") (pinfunction "1_1") (pintype "passive"))
      (node (ref "C12") (pin "1") (pinfunction "1_1") (pintype "passive"))
      (node (ref "C13") (pin "1") (pinfunction "1_1") (pintype "passive"))
      (node (ref "C14") (pin "1") (pinfunction "1_1") (pintype "passive"))
      (node (ref "C15") (pin "1") (pinfunction "1_1") (pintype "passive"))
      (node (ref "C16") (pin "1") (pinfunction "1_1") (pintype "passive"))
      (node (ref "C18") (pin "1") (pinfunction "1_1") (pintype "passive"))
      (node (ref "C28") (pin "2") (pinfunction "2_2") (pintype "passive"))
      (node (ref "CN1") (pin "4") (pinfunction "4_4") (pintype "passive"))
      (node (ref "CN2") (pin "4") (pinfunction "4_4") (pintype "passive"))
      (node (ref "CN3") (pin "4") (pinfunction "4_4") (pintype "passive"))
      (node (ref "CN4") (pin "4") (pinfunction "4_4") (pintype "passive"))
      (node (ref "CN5") (pin "4") (pinfunction "4_4") (pintype "passive"))
      (node (ref "CN6") (pin "4") (pinfunction "4_4") (pintype "passive"))
      (node (ref "D4") (pin "2") (pinfunction "2_2") (pintype "passive"))
      (node (ref "L2") (pin "2") (pinfunction "2_2") (pintype "passive"))
      (node (ref "R11") (pin "2") (pinfunction "2_2") (pintype "passive"))
      (node (ref "R17") (pin "1") (pinfunction "1_1") (pintype "passive"))
      (node (ref "R5") (pin "1") (pinfunction "1_1") (pintype "passive"))
      (node (ref "U2") (pin "1") (pinfunction "IN_1") (pintype "passive"))
      (node (ref "U4") (pin "3") (pinfunction "VCC_3") (pintype "passive"))
    )
    (net (code "29") (name "24V") (class "Default")
      (node (ref "C19") (pin "1") (pinfunction "1_1") (pintype "passive"))
      (node (ref "C20") (pin "1") (pinfunction "1_1") (pintype "passive"))
      (node (ref "C23") (pin "1") (pinfunction "1_1") (pintype "passive"))
      (node (ref "C24") (pin "1") (pinfunction "1_1") (pintype "passive"))
      (node (ref "C25") (pin "1") (pinfunction "1_1") (pintype "passive"))
      (node (ref "C26") (pin "1") (pinfunction "1_1") (pintype "passive"))
      (node (ref "C27") (pin "1") (pinfunction "1_1") (pintype "passive"))
      (node (ref "Q1") (pin "2") (pinfunction "S_2") (pintype "passive"))
      (node (ref "R13") (pin "2") (pinfunction "2_2") (pintype "passive"))
      (node (ref "R14") (pin "1") (pinfunction "1_1") (pintype "passive"))
      (node (ref "R4") (pin "1") (pinfunction "1_1") (pintype "passive"))
      (node (ref "U3") (pin "5") (pinfunction "IN_5") (pintype "passive"))
    )
    (net (code "30") (name "24V_IN") (class "Default")
      (node (ref "P1") (pin "1") (pinfunction "PAD_VCC_1") (pintype "passive"))
      (node (ref "S2") (pin "1") (pinfunction "1_1") (pintype "passive"))
    )
    (net (code "31") (name "GND") (class "Default")
      (node (ref "C1") (pin "1") (pinfunction "1_1") (pintype "passive"))
      (node (ref "C10") (pin "2") (pinfunction "2_2") (pintype "passive"))
      (node (ref "C11") (pin "2") (pinfunction "2_2") (pintype "passive"))
      (node (ref "C12") (pin "2") (pinfunction "2_2") (pintype "passive"))
      (node (ref "C13") (pin "2") (pinfunction "2_2") (pintype "passive"))
      (node (ref "C14") (pin "2") (pinfunction "2_2") (pintype "passive"))
      (node (ref "C15") (pin "2") (pinfunction "2_2") (pintype "passive"))
      (node (ref "C16") (pin "2") (pinfunction "2_2") (pintype "passive"))
      (node (ref "C18") (pin "2") (pinfunction "2_2") (pintype "passive"))
      (node (ref "C19") (pin "2") (pinfunction "2_2") (pintype "passive"))
      (node (ref "C2") (pin "1") (pinfunction "1_1") (pintype "passive"))
      (node (ref "C20") (pin "2") (pinfunction "2_2") (pintype "passive"))
      (node (ref "C21") (pin "2") (pinfunction "2_2") (pintype "passive"))
      (node (ref "C22") (pin "2") (pinfunction "2_2") (pintype "passive"))
      (node (ref "C23") (pin "2") (pinfunction "2_2") (pintype "passive"))
      (node (ref "C24") (pin "2") (pinfunction "2_2") (pintype "passive"))
      (node (ref "C25") (pin "2") (pinfunction "2_2") (pintype "passive"))
      (node (ref "C26") (pin "2") (pinfunction "2_2") (pintype "passive"))
      (node (ref "C27") (pin "2") (pinfunction "2_2") (pintype "passive"))
      (node (ref "C28") (pin "1") (pinfunction "1_1") (pintype "passive"))
      (node (ref "C29") (pin "1") (pinfunction "1_1") (pintype "passive"))
      (node (ref "C3") (pin "1") (pinfunction "1_1") (pintype "passive"))
      (node (ref "C30") (pin "2") (pinfunction "2_2") (pintype "passive"))
      (node (ref "C31") (pin "2") (pinfunction "2_2") (pintype "passive"))
      (node (ref "C4") (pin "1") (pinfunction "1_1") (pintype "passive"))
      (node (ref "C5") (pin "2") (pinfunction "2_2") (pintype "passive"))
      (node (ref "C6") (pin "2") (pinfunction "2_2") (pintype "passive"))
      (node (ref "C7") (pin "2") (pinfunction "2_2") (pintype "passive"))
      (node (ref "C8") (pin "2") (pinfunction "2_2") (pintype "passive"))
      (node (ref "C9") (pin "2") (pinfunction "2_2") (pintype "passive"))
      (node (ref "CN1") (pin "3") (pinfunction "3_3") (pintype "passive"))
      (node (ref "CN1") (pin "5") (pinfunction "5_5") (pintype "passive"))
      (node (ref "CN1") (pin "6") (pinfunction "6_6") (pintype "passive"))
      (node (ref "CN2") (pin "3") (pinfunction "3_3") (pintype "passive"))
      (node (ref "CN2") (pin "5") (pinfunction "5_5") (pintype "passive"))
      (node (ref "CN2") (pin "6") (pinfunction "6_6") (pintype "passive"))
      (node (ref "CN3") (pin "3") (pinfunction "3_3") (pintype "passive"))
      (node (ref "CN3") (pin "5") (pinfunction "5_5") (pintype "passive"))
      (node (ref "CN3") (pin "6") (pinfunction "6_6") (pintype "passive"))
      (node (ref "CN4") (pin "3") (pinfunction "3_3") (pintype "passive"))
      (node (ref "CN4") (pin "5") (pinfunction "5_5") (pintype "passive"))
      (node (ref "CN4") (pin "6") (pinfunction "6_6") (pintype "passive"))
      (node (ref "CN5") (pin "3") (pinfunction "3_3") (pintype "passive"))
      (node (ref "CN5") (pin "5") (pinfunction "5_5") (pintype "passive"))
      (node (ref "CN5") (pin "6") (pinfunction "6_6") (pintype "passive"))
      (node (ref "CN6") (pin "3") (pinfunction "3_3") (pintype "passive"))
      (node (ref "CN6") (pin "5") (pinfunction "5_5") (pintype "passive"))
      (node (ref "CN6") (pin "6") (pinfunction "6_6") (pintype "passive"))
      (node (ref "CN7") (pin "3") (pinfunction "3_3") (pintype "passive"))
      (node (ref "CN7") (pin "4") (pinfunction "4_4") (pintype "passive"))
      (node (ref "D1") (pin "2") (pinfunction "2_2") (pintype "passive"))
      (node (ref "D10") (pin "1") (pinfunction "A_1") (pintype "passive"))
      (node (ref "D11") (pin "1") (pinfunction "A_1") (pintype "passive"))
      (node (ref "D12") (pin "1") (pinfunction "A_1") (pintype "passive"))
      (node (ref "D13") (pin "1") (pinfunction "A_1") (pintype "passive"))
      (node (ref "D14") (pin "2") (pinfunction "2_2") (pintype "passive"))
      (node (ref "D15") (pin "2") (pinfunction "2_2") (pintype "passive"))
      (node (ref "D16") (pin "2") (pinfunction "2_2") (pintype "passive"))
      (node (ref "D19") (pin "1") (pinfunction "A_1") (pintype "passive"))
      (node (ref "D2") (pin "2") (pinfunction "2_2") (pintype "passive"))
      (node (ref "D20") (pin "1") (pinfunction "A_1") (pintype "passive"))
      (node (ref "D21") (pin "1") (pinfunction "A_1") (pintype "passive"))
      (node (ref "D22") (pin "1") (pinfunction "A_1") (pintype "passive"))
      (node (ref "D23") (pin "1") (pinfunction "A_1") (pintype "passive"))
      (node (ref "D24") (pin "1") (pinfunction "A_1") (pintype "passive"))
      (node (ref "D25") (pin "1") (pinfunction "A_1") (pintype "passive"))
      (node (ref "D26") (pin "1") (pinfunction "A_1") (pintype "passive"))
      (node (ref "D3") (pin "2") (pinfunction "2_2") (pintype "passive"))
      (node (ref "D8") (pin "1") (pinfunction "A_1") (pintype "passive"))
      (node (ref "D9") (pin "1") (pinfunction "A_1") (pintype "passive"))
      (node (ref "P2") (pin "1") (pinfunction "PAD_VCC_1") (pintype "passive"))
      (node (ref "R10") (pin "1") (pinfunction "1_1") (pintype "passive"))
      (node (ref "R12") (pin "1") (pinfunction "1_1") (pintype "passive"))
      (node (ref "R15") (pin "2") (pinfunction "2_2") (pintype "passive"))
      (node (ref "R16") (pin "2") (pinfunction "2_2") (pintype "passive"))
      (node (ref "R32") (pin "2") (pinfunction "2_2") (pintype "passive"))
      (node (ref "R8") (pin "1") (pinfunction "1_1") (pintype "passive"))
      (node (ref "R9") (pin "1") (pinfunction "1_1") (pintype "passive"))
      (node (ref "S1") (pin "3") (pinfunction "3_3") (pintype "passive"))
      (node (ref "S1") (pin "4") (pinfunction "4_4") (pintype "passive"))
      (node (ref "U1") (pin "12") (pinfunction "VSSA_12") (pintype "passive"))
      (node (ref "U1") (pin "18") (pinfunction "VSS_4_18") (pintype "passive"))
      (node (ref "U1") (pin "31") (pinfunction "VSS_1_31") (pintype "passive"))
      (node (ref "U1") (pin "47") (pinfunction "VSS_2_47") (pintype "passive"))
      (node (ref "U1") (pin "63") (pinfunction "VSS_3_63") (pintype "passive"))
      (node (ref "U2") (pin "2") (pinfunction "GND_2") (pintype "passive"))
      (node (ref "U3") (pin "3") (pinfunction "GND_3") (pintype "passive"))
      (node (ref "U3") (pin "4") (pinfunction "GND_4") (pintype "passive"))
      (node (ref "U4") (pin "2") (pinfunction "GND_2") (pintype "passive"))
      (node (ref "U4") (pin "8") (pinfunction "S_8") (pintype "passive"))
      (node (ref "X1") (pin "2") (pinfunction "GND_2") (pintype "passive"))
    )
    (net (code "32") (name "Net-(D1-Pad1)") (class "Default")
      (node (ref "D1") (pin "1") (pinfunction "1_1") (pintype "passive"))
      (node (ref "R4") (pin "2") (pinfunction "2_2") (pintype "passive"))
    )
    (net (code "33") (name "Net-(D2-Pad1)") (class "Default")
      (node (ref "D2") (pin "1") (pinfunction "1_1") (pintype "passive"))
      (node (ref "R5") (pin "2") (pinfunction "2_2") (pintype "passive"))
    )
    (net (code "34") (name "Net-(D3-Pad1)") (class "Default")
      (node (ref "D3") (pin "1") (pinfunction "1_1") (pintype "passive"))
      (node (ref "R7") (pin "2") (pinfunction "2_2") (pintype "passive"))
    )
    (net (code "35") (name "Net-(D8-C)") (class "Default")
      (node (ref "CN1") (pin "1") (pinfunction "1_1") (pintype "passive"))
      (node (ref "D5") (pin "2") (pinfunction "2_2") (pintype "passive"))
      (node (ref "D8") (pin "2") (pinfunction "C_2") (pintype "passive"))
    )
    (net (code "36") (name "Net-(D9-C)") (class "Default")
      (node (ref "CN1") (pin "2") (pinfunction "2_2") (pintype "passive"))
      (node (ref "D9") (pin "2") (pinfunction "C_2") (pintype "passive"))
      (node (ref "R21") (pin "1") (pinfunction "1_1") (pintype "passive"))
    )
    (net (code "37") (name "Net-(D10-C)") (class "Default")
      (node (ref "CN2") (pin "1") (pinfunction "1_1") (pintype "passive"))
      (node (ref "D10") (pin "2") (pinfunction "C_2") (pintype "passive"))
      (node (ref "D6") (pin "2") (pinfunction "2_2") (pintype "passive"))
    )
    (net (code "38") (name "Net-(D11-C)") (class "Default")
      (node (ref "CN2") (pin "2") (pinfunction "2_2") (pintype "passive"))
      (node (ref "D11") (pin "2") (pinfunction "C_2") (pintype "passive"))
      (node (ref "R22") (pin "1") (pinfunction "1_1") (pintype "passive"))
    )
    (net (code "39") (name "Net-(D12-C)") (class "Default")
      (node (ref "CN3") (pin "1") (pinfunction "1_1") (pintype "passive"))
      (node (ref "D12") (pin "2") (pinfunction "C_2") (pintype "passive"))
      (node (ref "D7") (pin "2") (pinfunction "2_2") (pintype "passive"))
    )
    (net (code "40") (name "Net-(D13-C)") (class "Default")
      (node (ref "CN3") (pin "2") (pinfunction "2_2") (pintype "passive"))
      (node (ref "D13") (pin "2") (pinfunction "C_2") (pintype "passive"))
      (node (ref "R23") (pin "1") (pinfunction "1_1") (pintype "passive"))
    )
    (net (code "41") (name "Net-(D14-Pad1)") (class "Default")
      (node (ref "D14") (pin "1") (pinfunction "1_1") (pintype "passive"))
      (node (ref "R24") (pin "2") (pinfunction "2_2") (pintype "passive"))
    )
    (net (code "42") (name "Net-(D15-Pad1)") (class "Default")
      (node (ref "D15") (pin "1") (pinfunction "1_1") (pintype "passive"))
      (node (ref "R25") (pin "2") (pinfunction "2_2") (pintype "passive"))
    )
    (net (code "43") (name "Net-(D16-Pad1)") (class "Default")
      (node (ref "D16") (pin "1") (pinfunction "1_1") (pintype "passive"))
      (node (ref "R26") (pin "2") (pinfunction "2_2") (pintype "passive"))
    )
    (net (code "44") (name "Net-(D19-C)") (class "Default")
      (node (ref "CN4") (pin "1") (pinfunction "1_1") (pintype "passive"))
      (node (ref "D17") (pin "2") (pinfunction "2_2") (pintype "passive"))
      (node (ref "D19") (pin "2") (pinfunction "C_2") (pintype "passive"))
    )
    (net (code "45") (name "Net-(D20-C)") (class "Default")
      (node (ref "CN4") (pin "2") (pinfunction "2_2") (pintype "passive"))
      (node (ref "D20") (pin "2") (pinfunction "C_2") (pintype "passive"))
      (node (ref "R29") (pin "1") (pinfunction "1_1") (pintype "passive"))
    )
    (net (code "46") (name "Net-(D21-C)") (class "Default")
      (node (ref "CN5") (pin "1") (pinfunction "1_1") (pintype "passive"))
      (node (ref "D18") (pin "2") (pinfunction "2_2") (pintype "passive"))
      (node (ref "D21") (pin "2") (pinfunction "C_2") (pintype "passive"))
    )
    (net (code "47") (name "Net-(D22-C)") (class "Default")
      (node (ref "CN5") (pin "2") (pinfunction "2_2") (pintype "passive"))
      (node (ref "D22") (pin "2") (pinfunction "C_2") (pintype "passive"))
      (node (ref "R30") (pin "1") (pinfunction "1_1") (pintype "passive"))
    )
    (net (code "48") (name "Net-(Q1-D)") (class "Default")
      (node (ref "Q1") (pin "3") (pinfunction "D_3") (pintype "passive"))
      (node (ref "S2") (pin "2") (pinfunction "2_2") (pintype "passive"))
    )
    (net (code "49") (name "Net-(Q1-G)") (class "Default")
      (node (ref "Q1") (pin "1") (pinfunction "G_1") (pintype "passive"))
      (node (ref "R14") (pin "2") (pinfunction "2_2") (pintype "passive"))
      (node (ref "R16") (pin "1") (pinfunction "1_1") (pintype "passive"))
    )
    (net (code "50") (name "Net-(U2-EN)") (class "Default")
      (node (ref "R17") (pin "2") (pinfunction "2_2") (pintype "passive"))
      (node (ref "U2") (pin "3") (pinfunction "EN_3") (pintype "passive"))
    )
    (net (code "51") (name "Net-(U3-BS)") (class "Default")
      (node (ref "C17") (pin "2") (pinfunction "2_2") (pintype "passive"))
      (node (ref "U3") (pin "7") (pinfunction "BS_7") (pintype "passive"))
    )
    (net (code "52") (name "Net-(U3-EN)") (class "Default")
      (node (ref "R12") (pin "2") (pinfunction "2_2") (pintype "passive"))
      (node (ref "R13") (pin "1") (pinfunction "1_1") (pintype "passive"))
      (node (ref "U3") (pin "8") (pinfunction "EN_8") (pintype "passive"))
    )
    (net (code "53") (name "Net-(U3-FB)") (class "Default")
      (node (ref "R10") (pin "2") (pinfunction "2_2") (pintype "passive"))
      (node (ref "R11") (pin "1") (pinfunction "1_1") (pintype "passive"))
      (node (ref "U3") (pin "1") (pinfunction "FB_1") (pintype "passive"))
    )
    (net (code "54") (name "Net-(U3-FS)") (class "Default")
      (node (ref "R15") (pin "1") (pinfunction "1_1") (pintype "passive"))
      (node (ref "U3") (pin "2") (pinfunction "FS_2") (pintype "passive"))
    )
    (net (code "55") (name "Net-(U3-LX)") (class "Default")
      (node (ref "C17") (pin "1") (pinfunction "1_1") (pintype "passive"))
      (node (ref "L2") (pin "1") (pinfunction "1_1") (pintype "passive"))
      (node (ref "U3") (pin "6") (pinfunction "LX_6") (pintype "passive"))
    )
    (net (code "56") (name "Net-(X1-OE{slash}#ST{slash}NC)") (class "Default")
      (node (ref "R1") (pin "1") (pinfunction "1_1") (pintype "passive"))
      (node (ref "X1") (pin "1") (pinfunction "OE/#ST/NC_1") (pintype "passive"))
    )
    (net (code "57") (name "Net-(X1-OUT)") (class "Default")
      (node (ref "R3") (pin "1") (pinfunction "1_1") (pintype "passive"))
      (node (ref "X1") (pin "3") (pinfunction "OUT_3") (pintype "passive"))
    )
    (net (code "58") (name "Net-(X1-VDD)") (class "Default")
      (node (ref "C2") (pin "2") (pinfunction "2_2") (pintype "passive"))
      (node (ref "L1") (pin "1") (pinfunction "1_1") (pintype "passive"))
      (node (ref "R1") (pin "2") (pinfunction "2_2") (pintype "passive"))
      (node (ref "X1") (pin "4") (pinfunction "VDD_4") (pintype "passive"))
    )
    (net (code "59") (name "unconnected-(U1-PA0-WKUP-Pad14)") (class "Default")
      (node (ref "U1") (pin "14") (pinfunction "PA0-WKUP_14") (pintype "passive"))
    )
    (net (code "60") (name "unconnected-(U1-PA1-Pad15)") (class "Default")
      (node (ref "U1") (pin "15") (pinfunction "PA1_15") (pintype "passive"))
    )
    (net (code "61") (name "unconnected-(U1-PA4-Pad20)") (class "Default")
      (node (ref "U1") (pin "20") (pinfunction "PA4_20") (pintype "passive"))
    )
    (net (code "62") (name "unconnected-(U1-PA5-Pad21)") (class "Default")
      (node (ref "U1") (pin "21") (pinfunction "PA5_21") (pintype "passive"))
    )
    (net (code "63") (name "unconnected-(U1-PA6-Pad22)") (class "Default")
      (node (ref "U1") (pin "22") (pinfunction "PA6_22") (pintype "passive"))
    )
    (net (code "64") (name "unconnected-(U1-PA7-Pad23)") (class "Default")
      (node (ref "U1") (pin "23") (pinfunction "PA7_23") (pintype "passive"))
    )
    (net (code "65") (name "unconnected-(U1-PA8-Pad41)") (class "Default")
      (node (ref "U1") (pin "41") (pinfunction "PA8_41") (pintype "passive"))
    )
    (net (code "66") (name "unconnected-(U1-PA15-Pad50)") (class "Default")
      (node (ref "U1") (pin "50") (pinfunction "PA15_50") (pintype "passive"))
    )
    (net (code "67") (name "unconnected-(U1-PB0-Pad26)") (class "Default")
      (node (ref "U1") (pin "26") (pinfunction "PB0_26") (pintype "passive"))
    )
    (net (code "68") (name "unconnected-(U1-PB1-Pad27)") (class "Default")
      (node (ref "U1") (pin "27") (pinfunction "PB1_27") (pintype "passive"))
    )
    (net (code "69") (name "unconnected-(U1-PB3-Pad55)") (class "Default")
      (node (ref "U1") (pin "55") (pinfunction "PB3_55") (pintype "passive"))
    )
    (net (code "70") (name "unconnected-(U1-PB4-Pad56)") (class "Default")
      (node (ref "U1") (pin "56") (pinfunction "PB4_56") (pintype "passive"))
    )
    (net (code "71") (name "unconnected-(U1-PB5-Pad57)") (class "Default")
      (node (ref "U1") (pin "57") (pinfunction "PB5_57") (pintype "passive"))
    )
    (net (code "72") (name "unconnected-(U1-PB6-Pad58)") (class "Default")
      (node (ref "U1") (pin "58") (pinfunction "PB6_58") (pintype "passive"))
    )
    (net (code "73") (name "unconnected-(U1-PB7-Pad59)") (class "Default")
      (node (ref "U1") (pin "59") (pinfunction "PB7_59") (pintype "passive"))
    )
    (net (code "74") (name "unconnected-(U1-PB8-Pad61)") (class "Default")
      (node (ref "U1") (pin "61") (pinfunction "PB8_61") (pintype "passive"))
    )
    (net (code "75") (name "unconnected-(U1-PB9-Pad62)") (class "Default")
      (node (ref "U1") (pin "62") (pinfunction "PB9_62") (pintype "passive"))
    )
    (net (code "76") (name "unconnected-(U1-PB15-Pad36)") (class "Default")
      (node (ref "U1") (pin "36") (pinfunction "PB15_36") (pintype "passive"))
    )
    (net (code "77") (name "unconnected-(U1-PC0-Pad8)") (class "Default")
      (node (ref "U1") (pin "8") (pinfunction "PC0_8") (pintype "passive"))
    )
    (net (code "78") (name "unconnected-(U1-PC1-Pad9)") (class "Default")
      (node (ref "U1") (pin "9") (pinfunction "PC1_9") (pintype "passive"))
    )
    (net (code "79") (name "unconnected-(U1-PC2-Pad10)") (class "Default")
      (node (ref "U1") (pin "10") (pinfunction "PC2_10") (pintype "passive"))
    )
    (net (code "80") (name "unconnected-(U1-PC3-Pad11)") (class "Default")
      (node (ref "U1") (pin "11") (pinfunction "PC3_11") (pintype "passive"))
    )
    (net (code "81") (name "unconnected-(U1-PC4-Pad24)") (class "Default")
      (node (ref "U1") (pin "24") (pinfunction "PC4_24") (pintype "passive"))
    )
    (net (code "82") (name "unconnected-(U1-PC5-Pad25)") (class "Default")
      (node (ref "U1") (pin "25") (pinfunction "PC5_25") (pintype "passive"))
    )
    (net (code "83") (name "unconnected-(U1-PC6-Pad37)") (class "Default")
      (node (ref "U1") (pin "37") (pinfunction "PC6_37") (pintype "passive"))
    )
    (net (code "84") (name "unconnected-(U1-PC13-TAMPER-RTC-Pad2)") (class "Default")
      (node (ref "U1") (pin "2") (pinfunction "PC13-TAMPER-RTC_2") (pintype "passive"))
    )
    (net (code "85") (name "unconnected-(U1-PC14-OSC32_IN-Pad3)") (class "Default")
      (node (ref "U1") (pin "3") (pinfunction "PC14-OSC32_IN_3") (pintype "passive"))
    )
    (net (code "86") (name "unconnected-(U1-PC15-OSC32_OUT-Pad4)") (class "Default")
      (node (ref "U1") (pin "4") (pinfunction "PC15-OSC32_OUT_4") (pintype "passive"))
    )
    (net (code "87") (name "unconnected-(U1-PD1-OSC_OUT-Pad6)") (class "Default")
      (node (ref "U1") (pin "6") (pinfunction "PD1-OSC_OUT_6") (pintype "passive"))
    )
    (net (code "88") (name "unconnected-(U2-NC-Pad4)") (class "Default")
      (node (ref "U2") (pin "4") (pinfunction "NC_4") (pintype "passive+no_connect"))
    )
  )
)
